# frontpanel.net
KiCad netlist of a schematic drawn in Altium Designer
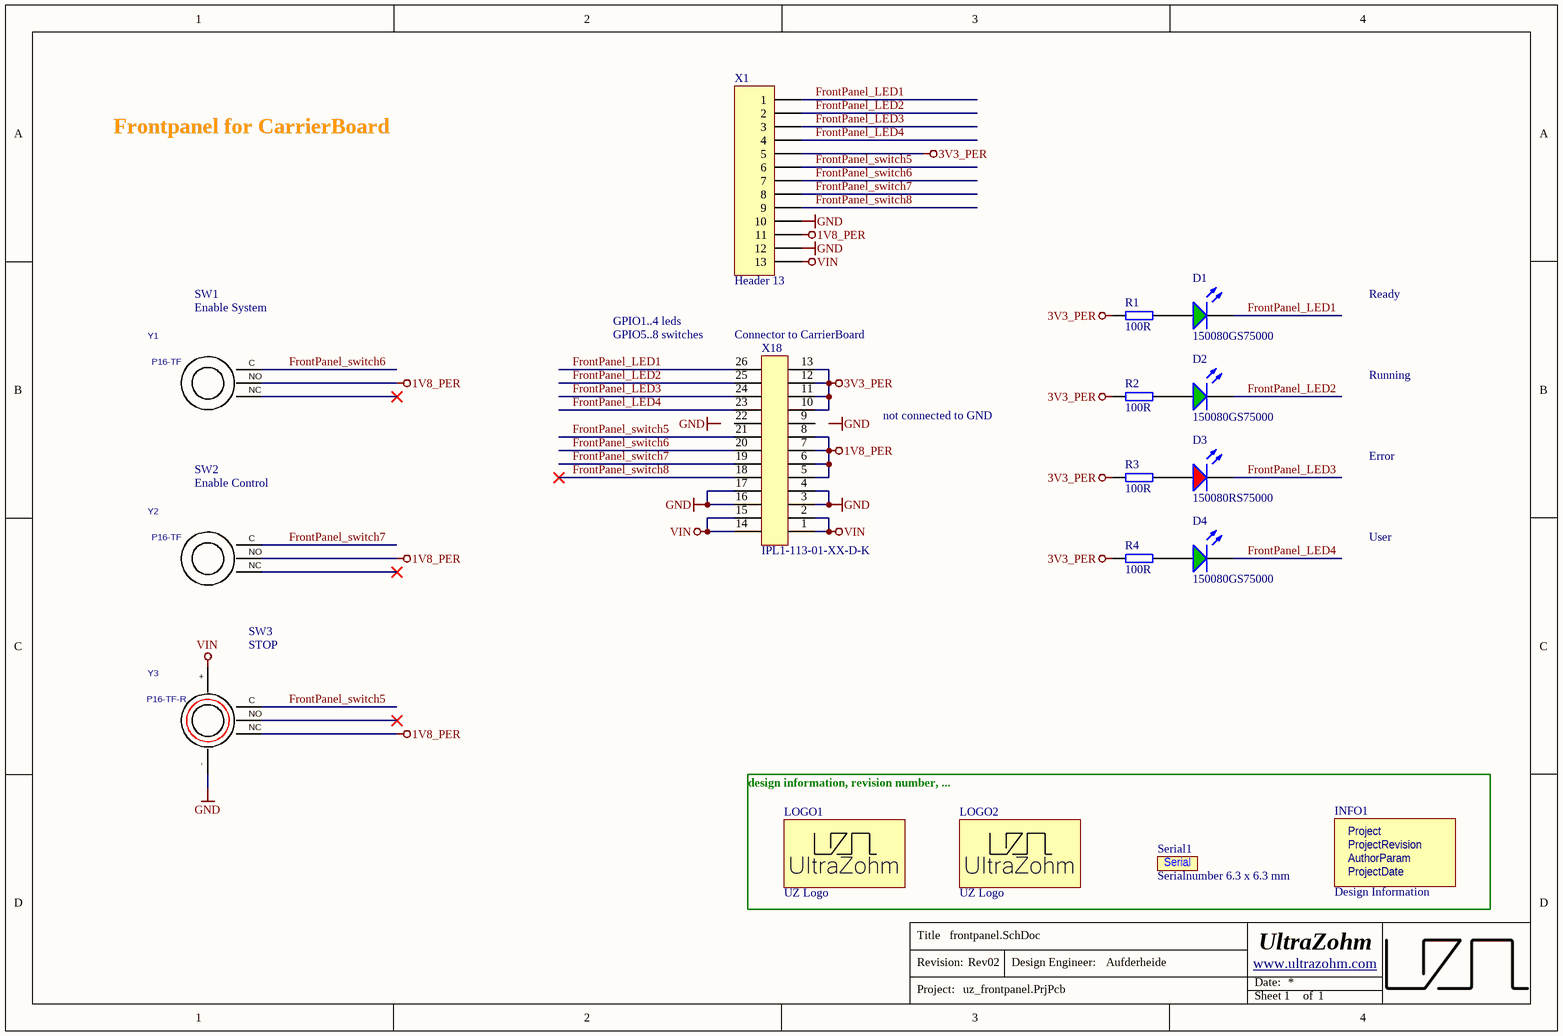
[diagram p0: frontpanel.SchDoc]

(export (version "E")
  (design (tool "Eeschema 10.0.6"))
  (components
    (comp (ref "D1")
      (value "150080GS75000")
      (footprint "LEDM2012X80N")
      (description "WL-SMCW SMD Mono-color Chip LED Waterclear Green 0805")
      (fields
        (field (name "MANUFACTURER") "Wuerth Elektronik")
        (field (name "LCSC PART #") "C2297")
        (field (name "CREATED FROM") "MGremer")
      )
      (libsource (lib "user") (part "LED_Green"))
    )
    (comp (ref "D2")
      (value "150080GS75000")
      (footprint "LEDM2012X80N")
      (description "WL-SMCW SMD Mono-color Chip LED Waterclear Green 0805")
      (fields
        (field (name "MANUFACTURER") "Wuerth Elektronik")
        (field (name "LCSC PART #") "C2297")
        (field (name "CREATED FROM") "MGremer")
      )
      (libsource (lib "user") (part "LED_Green"))
    )
    (comp (ref "D3")
      (value "150080RS75000")
      (footprint "LEDM2012X80N")
      (description "WL-SMCW SMD Mono-color Chip LED Waterclear Red 0805")
      (fields
        (field (name "MANUFACTURER") "Wuerth Elektronik")
        (field (name "LCSC PART #") "C84256")
        (field (name "CREATED FROM") "MGremer")
      )
      (libsource (lib "user") (part "LED_Red"))
    )
    (comp (ref "D4")
      (value "150080GS75000")
      (footprint "LEDM2012X80N")
      (description "WL-SMCW SMD Mono-color Chip LED Waterclear Green 0805")
      (fields
        (field (name "MANUFACTURER") "Wuerth Elektronik")
        (field (name "LCSC PART #") "C2297")
        (field (name "CREATED FROM") "MGremer")
      )
      (libsource (lib "user") (part "LED_Green"))
    )
    (comp (ref "INFO1")
      (value "Design Information")
      (footprint "Design_info")
      (fields (field (name "MANUFACTURER") "UltraZohm") (field (name "CREATED FROM") "MGremer"))
      (libsource (lib "user") (part "Design_info"))
    )
    (comp (ref "LOGO1")
      (value "UZ Logo")
      (footprint "UZ_Logo_small")
      (fields
        (field (name "MANUFACTURER PART NUMBER") "Logo small")
        (field (name "MANUFACTURER") "UltraZohm")
        (field (name "CREATED") "Jan2021_Liegmann")
        (field (name "CREATED FROM") "MGremer")
      )
      (libsource (lib "user") (part "UZ Logo"))
    )
    (comp (ref "LOGO2")
      (value "UZ Logo")
      (footprint "UZ_Logo_small")
      (fields
        (field (name "MANUFACTURER PART NUMBER") "Logo small")
        (field (name "MANUFACTURER") "UltraZohm")
        (field (name "CREATED") "Jan2021_Liegmann")
        (field (name "CREATED FROM") "MGremer")
      )
      (libsource (lib "user") (part "UZ Logo"))
    )
    (comp (ref "R1")
      (value "100R")
      (footprint "RES 0805_2012")
      (description "SMD resistor 1%")
      (fields
        (field (name "MANUFACTURER PART NUMBER") "CR0805FX-1000ELF")
        (field (name "MANUFACTURER") "Bourns")
        (field (name "CREATED FROM") "MGremer")
      )
      (libsource (lib "user") (part "Resistor"))
    )
    (comp (ref "R2")
      (value "100R")
      (footprint "RES 0805_2012")
      (description "SMD resistor 1%")
      (fields
        (field (name "MANUFACTURER PART NUMBER") "CR0805FX-1000ELF")
        (field (name "MANUFACTURER") "Bourns")
        (field (name "CREATED FROM") "MGremer")
      )
      (libsource (lib "user") (part "Resistor"))
    )
    (comp (ref "R3")
      (value "100R")
      (footprint "RES 0805_2012")
      (description "SMD resistor 1%")
      (fields
        (field (name "MANUFACTURER PART NUMBER") "CR0805FX-1000ELF")
        (field (name "MANUFACTURER") "Bourns")
        (field (name "CREATED FROM") "MGremer")
      )
      (libsource (lib "user") (part "Resistor"))
    )
    (comp (ref "R4")
      (value "100R")
      (footprint "RES 0805_2012")
      (description "SMD resistor 1%")
      (fields
        (field (name "MANUFACTURER PART NUMBER") "CR0805FX-1000ELF")
        (field (name "MANUFACTURER") "Bourns")
        (field (name "CREATED FROM") "MGremer")
      )
      (libsource (lib "user") (part "Resistor"))
    )
    (comp (ref "Serial1")
      (value "Serialnumber 6.3 x 6.3 mm")
      (footprint "SERIAL_6.3X6.3MM")
      (description "Serial Number")
      (fields
        (field (name "MANUFACTURER") "UltraZohm")
        (field (name "CREATED") "2018_09_18_AGeiger")
        (field (name "CREATED FROM") "MGremer")
      )
      (libsource (lib "user") (part "SerialNumber"))
    )
    (comp (ref "X1")
      (value "Header 13")
      (footprint "HDR1X13")
      (description "Header, 13-Pin")
      (fields (field (name "PUBLISHER") "Altium Limited"))
      (libsource (lib "Miscellaneous Connectors") (part "Header 13"))
    )
    (comp (ref "X18")
      (value "IPL1-113-01-XX-D-K")
      (footprint "IPL1-113-01-XX-D-K")
      (description "2.54 mm Double Row Termin Assembly (THT)")
      (fields (field (name "MANUFACTURER") "SAMTEC") (field (name "CREATED FROM") "MGremer"))
      (libsource (lib "user") (part "IPL1-113-XX-X-D-K"))
    )
    (comp (ref "Y1")
      (value "P16-TF")
      (footprint "P16-TF")
      (description "Stainless steel push botton 0.63 inch flat")
      (fields (field (name "MANUFACTURER") "Metzler") (field (name "CREATED FROM") "MGremer"))
      (libsource (lib "user") (part "P16-TR"))
    )
    (comp (ref "Y2")
      (value "P16-TF")
      (footprint "P16-TF")
      (description "Stainless steel push botton 0.63 inch flat")
      (fields (field (name "MANUFACTURER") "Metzler") (field (name "CREATED FROM") "MGremer"))
      (libsource (lib "user") (part "P16-TR"))
    )
    (comp (ref "Y3")
      (value "P16-TF-R")
      (footprint "P16-TF-R")
      (description "Stainless steel push botton 0.63 inch flat LED Ring red")
      (fields (field (name "MANUFACTURER") "Metzler") (field (name "CREATED FROM") "MGremer"))
      (libsource (lib "user") (part "P16-TR-R"))
    )
  )
  (nets
    (net (code "2") (name "/FrontPanel_LED1") (class "Default")
      (node (ref "D1") (pin "1") (pinfunction "K_1") (pintype "passive"))
      (node (ref "X1") (pin "1") (pinfunction "1_1") (pintype "passive"))
      (node (ref "X18") (pin "26") (pinfunction "26_26") (pintype "passive"))
    )
    (net (code "3") (name "/FrontPanel_LED2") (class "Default")
      (node (ref "D2") (pin "1") (pinfunction "K_1") (pintype "passive"))
      (node (ref "X1") (pin "2") (pinfunction "2_2") (pintype "passive"))
      (node (ref "X18") (pin "25") (pinfunction "25_25") (pintype "passive"))
    )
    (net (code "4") (name "/FrontPanel_LED3") (class "Default")
      (node (ref "D3") (pin "1") (pinfunction "K_1") (pintype "passive"))
      (node (ref "X1") (pin "3") (pinfunction "3_3") (pintype "passive"))
      (node (ref "X18") (pin "24") (pinfunction "24_24") (pintype "passive"))
    )
    (net (code "5") (name "/FrontPanel_LED4") (class "Default")
      (node (ref "D4") (pin "1") (pinfunction "K_1") (pintype "passive"))
      (node (ref "X1") (pin "4") (pinfunction "4_4") (pintype "passive"))
      (node (ref "X18") (pin "23") (pinfunction "23_23") (pintype "passive"))
    )
    (net (code "6") (name "/FrontPanel_switch5") (class "Default")
      (node (ref "X1") (pin "6") (pinfunction "6_6") (pintype "passive"))
      (node (ref "X18") (pin "21") (pinfunction "21_21") (pintype "passive"))
      (node (ref "Y3") (pin "C") (pinfunction "C_C") (pintype "passive"))
    )
    (net (code "7") (name "/FrontPanel_switch6") (class "Default")
      (node (ref "X1") (pin "7") (pinfunction "7_7") (pintype "passive"))
      (node (ref "X18") (pin "20") (pinfunction "20_20") (pintype "passive"))
      (node (ref "Y1") (pin "C") (pinfunction "C_C") (pintype "passive"))
    )
    (net (code "8") (name "/FrontPanel_switch7") (class "Default")
      (node (ref "X1") (pin "8") (pinfunction "8_8") (pintype "passive"))
      (node (ref "X18") (pin "19") (pinfunction "19_19") (pintype "passive"))
      (node (ref "Y2") (pin "C") (pinfunction "C_C") (pintype "passive"))
    )
    (net (code "9") (name "/FrontPanel_switch8") (class "Default")
      (node (ref "X1") (pin "9") (pinfunction "9_9") (pintype "passive"))
      (node (ref "X18") (pin "18") (pinfunction "18_18") (pintype "passive"))
    )
    (net (code "10") (name "1V8_PER") (class "Default")
      (node (ref "X1") (pin "11") (pinfunction "11_11") (pintype "passive"))
      (node (ref "X18") (pin "5") (pinfunction "5_5") (pintype "passive"))
      (node (ref "X18") (pin "6") (pinfunction "6_6") (pintype "passive"))
      (node (ref "X18") (pin "7") (pinfunction "7_7") (pintype "passive"))
      (node (ref "X18") (pin "8") (pinfunction "8_8") (pintype "passive"))
      (node (ref "Y1") (pin "NO") (pinfunction "NO_NO") (pintype "passive"))
      (node (ref "Y2") (pin "NO") (pinfunction "NO_NO") (pintype "passive"))
      (node (ref "Y3") (pin "NC") (pinfunction "NC_NC") (pintype "passive"))
    )
    (net (code "11") (name "3V3_PER") (class "Default")
      (node (ref "R1") (pin "1") (pinfunction "1_1") (pintype "passive"))
      (node (ref "R2") (pin "1") (pinfunction "1_1") (pintype "passive"))
      (node (ref "R3") (pin "1") (pinfunction "1_1") (pintype "passive"))
      (node (ref "R4") (pin "1") (pinfunction "1_1") (pintype "passive"))
      (node (ref "X1") (pin "5") (pinfunction "5_5") (pintype "passive"))
      (node (ref "X18") (pin "10") (pinfunction "10_10") (pintype "passive"))
      (node (ref "X18") (pin "11") (pinfunction "11_11") (pintype "passive"))
      (node (ref "X18") (pin "12") (pinfunction "12_12") (pintype "passive"))
      (node (ref "X18") (pin "13") (pinfunction "13_13") (pintype "passive"))
    )
    (net (code "12") (name "GND") (class "Default")
      (node (ref "X1") (pin "10") (pinfunction "10_10") (pintype "passive"))
      (node (ref "X1") (pin "12") (pinfunction "12_12") (pintype "passive"))
      (node (ref "X18") (pin "16") (pinfunction "16_16") (pintype "passive"))
      (node (ref "X18") (pin "17") (pinfunction "17_17") (pintype "passive"))
      (node (ref "X18") (pin "3") (pinfunction "3_3") (pintype "passive"))
      (node (ref "X18") (pin "4") (pinfunction "4_4") (pintype "passive"))
      (node (ref "Y3") (pin "-") (pinfunction "-_-") (pintype "passive"))
    )
    (net (code "13") (name "Net-(D1-A)") (class "Default")
      (node (ref "D1") (pin "2") (pinfunction "A_2") (pintype "passive"))
      (node (ref "R1") (pin "2") (pinfunction "2_2") (pintype "passive"))
    )
    (net (code "14") (name "Net-(D2-A)") (class "Default")
      (node (ref "D2") (pin "2") (pinfunction "A_2") (pintype "passive"))
      (node (ref "R2") (pin "2") (pinfunction "2_2") (pintype "passive"))
    )
    (net (code "15") (name "Net-(D3-A)") (class "Default")
      (node (ref "D3") (pin "2") (pinfunction "A_2") (pintype "passive"))
      (node (ref "R3") (pin "2") (pinfunction "2_2") (pintype "passive"))
    )
    (net (code "16") (name "Net-(D4-A)") (class "Default")
      (node (ref "D4") (pin "2") (pinfunction "A_2") (pintype "passive"))
      (node (ref "R4") (pin "2") (pinfunction "2_2") (pintype "passive"))
    )
    (net (code "17") (name "VIN") (class "Default")
      (node (ref "X1") (pin "13") (pinfunction "13_13") (pintype "passive"))
      (node (ref "X18") (pin "1") (pinfunction "1_1") (pintype "passive"))
      (node (ref "X18") (pin "14") (pinfunction "14_14") (pintype "passive"))
      (node (ref "X18") (pin "15") (pinfunction "15_15") (pintype "passive"))
      (node (ref "X18") (pin "2") (pinfunction "2_2") (pintype "passive"))
      (node (ref "Y3") (pin "+") (pinfunction "+_+") (pintype "passive"))
    )
    (net (code "18") (name "unconnected-(X18-Pad9)") (class "Default")
      (node (ref "X18") (pin "9") (pinfunction "9_9") (pintype "passive"))
    )
    (net (code "19") (name "unconnected-(X18-Pad22)") (class "Default")
      (node (ref "X18") (pin "22") (pinfunction "22_22") (pintype "passive"))
    )
    (net (code "20") (name "unconnected-(Y1-PadNC)") (class "Default")
      (node (ref "Y1") (pin "NC") (pinfunction "NC_NC") (pintype "passive+no_connect"))
    )
    (net (code "21") (name "unconnected-(Y2-PadNC)") (class "Default")
      (node (ref "Y2") (pin "NC") (pinfunction "NC_NC") (pintype "passive+no_connect"))
    )
    (net (code "22") (name "unconnected-(Y3-PadNO)") (class "Default")
      (node (ref "Y3") (pin "NO") (pinfunction "NO_NO") (pintype "passive+no_connect"))
    )
  )
)
